# FAA.net
KiCad netlist of a schematic drawn in Altium Designer
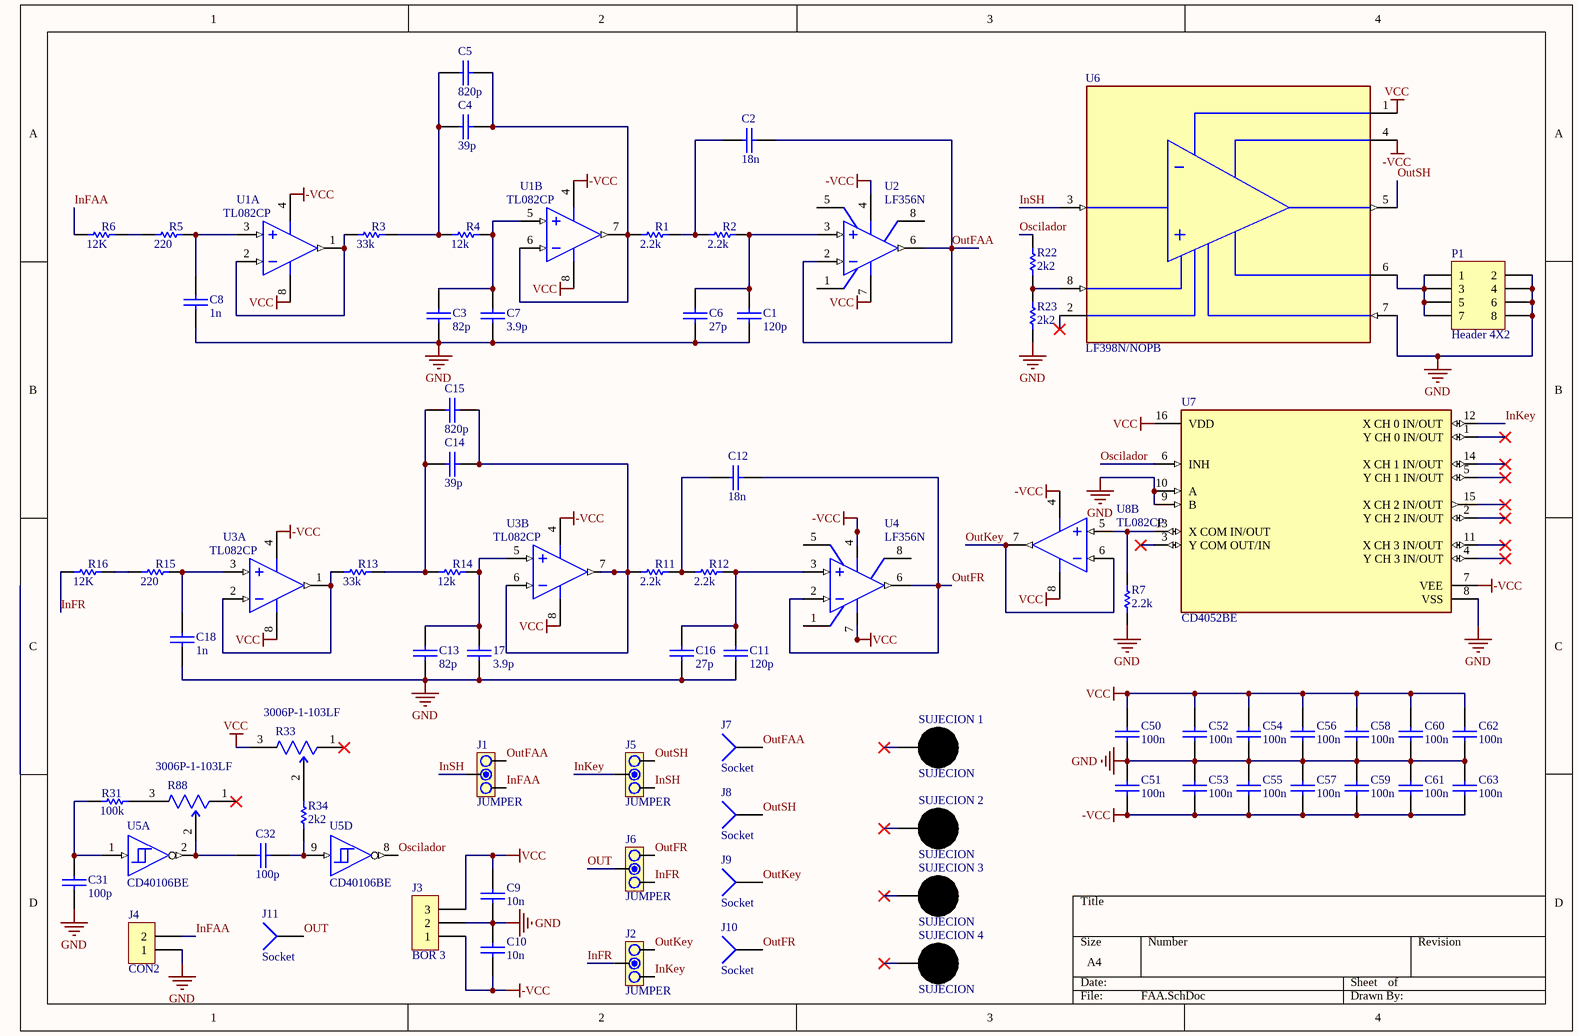
[diagram p0: FAA.SchDoc]

(export (version "E")
  (design (tool "Eeschema 10.0.6"))
  (components
    (comp (ref "17") (value "3.9p") (footprint "CAP200") (libsource (lib "LIB PIO IX") (part "CAP")))
    (comp (ref "C1") (value "120p") (footprint "CAP200") (libsource (lib "LIB PIO IX") (part "CAP")))
    (comp (ref "C2") (value "18n") (footprint "CAP200") (libsource (lib "LIB PIO IX") (part "CAP")))
    (comp (ref "C3") (value "82p") (footprint "CAP200") (libsource (lib "LIB PIO IX") (part "CAP")))
    (comp (ref "C4") (value "39p") (footprint "CAP200") (libsource (lib "LIB PIO IX") (part "CAP")))
    (comp (ref "C5") (value "820p") (footprint "CAP200") (libsource (lib "LIB PIO IX") (part "CAP")))
    (comp (ref "C6") (value "27p") (footprint "CAP200") (libsource (lib "LIB PIO IX") (part "CAP")))
    (comp (ref "C7") (value "3.9p") (footprint "CAP200") (libsource (lib "LIB PIO IX") (part "CAP")))
    (comp (ref "C8") (value "1n") (footprint "CAP200") (libsource (lib "LIB PIO IX") (part "CAP")))
    (comp (ref "C9") (value "10n") (footprint "CAP100") (libsource (lib "LIB PIO IX") (part "CAP")))
    (comp (ref "C10") (value "10n") (footprint "CAP100") (libsource (lib "LIB PIO IX") (part "CAP")))
    (comp (ref "C11") (value "120p") (footprint "CAP200") (libsource (lib "LIB PIO IX") (part "CAP")))
    (comp (ref "C12") (value "18n") (footprint "CAP200") (libsource (lib "LIB PIO IX") (part "CAP")))
    (comp (ref "C13") (value "82p") (footprint "CAP200") (libsource (lib "LIB PIO IX") (part "CAP")))
    (comp (ref "C14") (value "39p") (footprint "CAP200") (libsource (lib "LIB PIO IX") (part "CAP")))
    (comp (ref "C15") (value "820p") (footprint "CAP200") (libsource (lib "LIB PIO IX") (part "CAP")))
    (comp (ref "C16") (value "27p") (footprint "CAP200") (libsource (lib "LIB PIO IX") (part "CAP")))
    (comp (ref "C18") (value "1n") (footprint "CAP200") (libsource (lib "LIB PIO IX") (part "CAP")))
    (comp (ref "C31") (value "100p") (footprint "CAP200") (libsource (lib "LIB PIO IX") (part "CAP")))
    (comp (ref "C32") (value "100p") (footprint "CAP200") (libsource (lib "LIB PIO IX") (part "CAP")))
    (comp (ref "C50") (value "100n") (footprint "CAP100") (libsource (lib "LIB PIO IX") (part "CAP")))
    (comp (ref "C51") (value "100n") (footprint "CAP100") (libsource (lib "LIB PIO IX") (part "CAP")))
    (comp (ref "C52") (value "100n") (footprint "CAP100") (libsource (lib "LIB PIO IX") (part "CAP")))
    (comp (ref "C53") (value "100n") (footprint "CAP100") (libsource (lib "LIB PIO IX") (part "CAP")))
    (comp (ref "C54") (value "100n") (footprint "CAP100") (libsource (lib "LIB PIO IX") (part "CAP")))
    (comp (ref "C55") (value "100n") (footprint "CAP100") (libsource (lib "LIB PIO IX") (part "CAP")))
    (comp (ref "C56") (value "100n") (footprint "CAP100") (libsource (lib "LIB PIO IX") (part "CAP")))
    (comp (ref "C57") (value "100n") (footprint "CAP100") (libsource (lib "LIB PIO IX") (part "CAP")))
    (comp (ref "C58") (value "100n") (footprint "CAP100") (libsource (lib "LIB PIO IX") (part "CAP")))
    (comp (ref "C59") (value "100n") (footprint "CAP100") (libsource (lib "LIB PIO IX") (part "CAP")))
    (comp (ref "C60") (value "100n") (footprint "CAP100") (libsource (lib "LIB PIO IX") (part "CAP")))
    (comp (ref "C61") (value "100n") (footprint "CAP100") (libsource (lib "LIB PIO IX") (part "CAP")))
    (comp (ref "C62") (value "100n") (footprint "CAP100") (libsource (lib "LIB PIO IX") (part "CAP")))
    (comp (ref "C63") (value "100n") (footprint "CAP100") (libsource (lib "LIB PIO IX") (part "CAP")))
    (comp (ref "J1") (value "JUMPER") (footprint "JUMPER3") (libsource (lib "LIB PIO IX") (part "JUMPER3")))
    (comp (ref "J2") (value "JUMPER") (footprint "JUMPER3") (libsource (lib "LIB PIO IX") (part "JUMPER3")))
    (comp (ref "J3") (value "BOR 3") (footprint "BORNERA3") (libsource (lib "LIB PIO IX") (part "BORNERA 3")))
    (comp (ref "J4") (value "CON2") (footprint "SIP2") (libsource (lib "LIB PIO IX") (part "CON2")))
    (comp (ref "J5") (value "JUMPER") (footprint "JUMPER3") (libsource (lib "LIB PIO IX") (part "JUMPER3")))
    (comp (ref "J6") (value "JUMPER") (footprint "JUMPER3") (libsource (lib "LIB PIO IX") (part "JUMPER3")))
    (comp (ref "J7")
      (value "Socket")
      (footprint "PIN1")
      (fields (field (name "PUBLISHER") "Altium Limited"))
      (libsource (lib "Miscellaneous Connectors") (part "Socket"))
    )
    (comp (ref "J8")
      (value "Socket")
      (footprint "PIN1")
      (fields (field (name "PUBLISHER") "Altium Limited"))
      (libsource (lib "Miscellaneous Connectors") (part "Socket"))
    )
    (comp (ref "J9")
      (value "Socket")
      (footprint "PIN1")
      (fields (field (name "PUBLISHER") "Altium Limited"))
      (libsource (lib "Miscellaneous Connectors") (part "Socket"))
    )
    (comp (ref "J10")
      (value "Socket")
      (footprint "PIN1")
      (fields (field (name "PUBLISHER") "Altium Limited"))
      (libsource (lib "Miscellaneous Connectors") (part "Socket"))
    )
    (comp (ref "J11")
      (value "Socket")
      (footprint "PIN1")
      (fields (field (name "PUBLISHER") "Altium Limited"))
      (libsource (lib "Miscellaneous Connectors") (part "Socket"))
    )
    (comp (ref "P1")
      (value "Header 4X2")
      (footprint "HDR2X4")
      (description "Header, 4-Pin, Dual row")
      (fields (field (name "PUBLISHER") "Altium Limited"))
      (libsource (lib "Miscellaneous Connectors") (part "Header 4X2"))
    )
    (comp (ref "R1") (value "2.2k") (footprint "RES400") (libsource (lib "LIB PIO IX") (part "RES")))
    (comp (ref "R2") (value "2.2k") (footprint "RES400") (libsource (lib "LIB PIO IX") (part "RES")))
    (comp (ref "R3") (value "33k") (footprint "RES400") (libsource (lib "LIB PIO IX") (part "RES")))
    (comp (ref "R4") (value "12k") (footprint "RES400") (libsource (lib "LIB PIO IX") (part "RES")))
    (comp (ref "R5") (value "220") (footprint "RES400") (libsource (lib "LIB PIO IX") (part "RES")))
    (comp (ref "R6") (value "12K") (footprint "RES400") (libsource (lib "LIB PIO IX") (part "RES")))
    (comp (ref "R7") (value "2.2k") (footprint "RES400") (libsource (lib "LIB PIO IX") (part "RES")))
    (comp (ref "R11") (value "2.2k") (footprint "RES400") (libsource (lib "LIB PIO IX") (part "RES")))
    (comp (ref "R12") (value "2.2k") (footprint "RES400") (libsource (lib "LIB PIO IX") (part "RES")))
    (comp (ref "R13") (value "33k") (footprint "RES400") (libsource (lib "LIB PIO IX") (part "RES")))
    (comp (ref "R14") (value "12k") (footprint "RES400") (libsource (lib "LIB PIO IX") (part "RES")))
    (comp (ref "R15") (value "220") (footprint "RES400") (libsource (lib "LIB PIO IX") (part "RES")))
    (comp (ref "R16") (value "12K") (footprint "RES400") (libsource (lib "LIB PIO IX") (part "RES")))
    (comp (ref "R22") (value "2k2") (footprint "RES400") (libsource (lib "LIB PIO IX") (part "RES")))
    (comp (ref "R23") (value "2k2") (footprint "RES400") (libsource (lib "LIB PIO IX") (part "RES")))
    (comp (ref "R31") (value "100k") (footprint "RES400") (libsource (lib "LIB PIO IX") (part "RES")))
    (comp (ref "R33")
      (value "3006P-1-103LF")
      (footprint "FP-3006P-MFG")
      (description "TRIMMER 10KOHM 0.75W PC PIN SIDE")
      (fields (field (name "TOLERANCE") "10%"))
      (libsource (lib "Altium Content Vault") (part "ad0de4570dda44d2fdef8f57041519a"))
    )
    (comp (ref "R34") (value "2k2") (footprint "RES400") (libsource (lib "LIB PIO IX") (part "RES")))
    (comp (ref "R88")
      (value "3006P-1-103LF")
      (footprint "FP-3006P-MFG")
      (description "TRIMMER 10KOHM 0.75W PC PIN SIDE")
      (fields (field (name "TOLERANCE") "10%"))
      (libsource (lib "Altium Content Vault") (part "ad0de4570dda44d2fdef8f57041519a"))
    )
    (comp (ref "SUJECION 1")
      (value "SUJECION")
      (footprint "SUJECION (5.00MM - 3.50MM)")
      (libsource (lib "LIB2013") (part "SUJECION"))
    )
    (comp (ref "SUJECION 2")
      (value "SUJECION")
      (footprint "SUJECION (5.00MM - 3.50MM)")
      (libsource (lib "LIB2013") (part "SUJECION"))
    )
    (comp (ref "SUJECION 3")
      (value "SUJECION")
      (footprint "SUJECION (5.00MM - 3.50MM)")
      (libsource (lib "LIB2013") (part "SUJECION"))
    )
    (comp (ref "SUJECION 4")
      (value "SUJECION")
      (footprint "SUJECION (5.00MM - 3.50MM)")
      (libsource (lib "LIB2013") (part "SUJECION"))
    )
    (comp (ref "U1")
      (value "TL082CP")
      (footprint "P0008A")
      (description "JFET-Input Operational Amplifier, 7 to 36 V, 0 to 70 degC, 8-pin DIP (P8), Pb-Free (RoHS)")
      (fields (field (name "MANUFACTURER") "Texas Instruments"))
      (libsource (lib "Altium Content Vault") (part "TI-AMP-D6-2-8_D"))
    )
    (comp (ref "U2")
      (value "LF356N")
      (footprint "P0008A")
      (description "JFET Input Operational Amplifier, 8-pin MDIP")
      (fields (field (name "MANUFACTURER") "Texas Instruments"))
      (libsource (lib "Altium Content Vault") (part "AMP-OPA-LF156-8"))
    )
    (comp (ref "U3")
      (value "TL082CP")
      (footprint "P0008A")
      (description "JFET-Input Operational Amplifier, 7 to 36 V, 0 to 70 degC, 8-pin DIP (P8), Pb-Free (RoHS)")
      (fields (field (name "MANUFACTURER") "Texas Instruments"))
      (libsource (lib "Altium Content Vault") (part "TI-AMP-D6-2-8_D"))
    )
    (comp (ref "U4")
      (value "LF356N")
      (footprint "P0008A")
      (description "JFET Input Operational Amplifier, 8-pin MDIP")
      (fields (field (name "MANUFACTURER") "Texas Instruments"))
      (libsource (lib "Altium Content Vault") (part "AMP-OPA-LF156-8"))
    )
    (comp (ref "U5")
      (value "CD40106BE")
      (footprint "N0014A")
      (description "CMOS Hex Schmitt Triggers, N0014A, TUBE")
      (fields
        (field (name "MANUFACTURER") "Texas Instruments")
        (field (name "GENERIC PART NUMBER") "CD40106B")
      )
      (libsource (lib "Altium Content Vault") (part "TI-CD40XXXB-14-SCHMITT"))
    )
    (comp (ref "U6")
      (value "LF398N/NOPB")
      (footprint "FP-P0008A-MFG")
      (description "IC OPAMP SAMPL/HOLD 1 CIRC 8DIP")
      (libsource (lib "Altium Content Vault") (part "663395f396e52967eeae42d09f15be4"))
    )
    (comp (ref "U7")
      (value "CD4052BE")
      (footprint "FP-N0016A-MFG")
      (description "IC MUX/DEMUX DUAL 4X1 16DIP")
      (libsource (lib "Altium Content Vault") (part "f592c568caf548e7f28197573c85c05"))
    )
    (comp (ref "U8")
      (value "TL082CP")
      (footprint "P0008A")
      (description "JFET-Input Operational Amplifier, 7 to 36 V, 0 to 70 degC, 8-pin DIP (P8), Pb-Free (RoHS)")
      (fields (field (name "MANUFACTURER") "Texas Instruments"))
      (libsource (lib "Altium Content Vault") (part "TI-AMP-D6-2-8_D"))
    )
  )
  (nets
    (net (code "1") (name "-VCC") (class "Default")
      (node (ref "C10") (pin "2") (pinfunction "2_2") (pintype "passive"))
      (node (ref "C51") (pin "2") (pinfunction "2_2") (pintype "passive"))
      (node (ref "C53") (pin "2") (pinfunction "2_2") (pintype "passive"))
      (node (ref "C55") (pin "2") (pinfunction "2_2") (pintype "passive"))
      (node (ref "C57") (pin "2") (pinfunction "2_2") (pintype "passive"))
      (node (ref "C59") (pin "2") (pinfunction "2_2") (pintype "passive"))
      (node (ref "C61") (pin "2") (pinfunction "2_2") (pintype "passive"))
      (node (ref "C63") (pin "2") (pinfunction "2_2") (pintype "passive"))
      (node (ref "J3") (pin "1") (pinfunction "1_1") (pintype "passive"))
      (node (ref "U1") (pin "4") (pinfunction "VCC-_4") (pintype "power_in"))
      (node (ref "U2") (pin "4") (pinfunction "V-_4") (pintype "power_in"))
      (node (ref "U3") (pin "4") (pinfunction "VCC-_4") (pintype "power_in"))
      (node (ref "U4") (pin "4") (pinfunction "V-_4") (pintype "power_in"))
      (node (ref "U6") (pin "4") (pinfunction "V-_4") (pintype "power_in"))
      (node (ref "U7") (pin "7") (pinfunction "VEE_7") (pintype "power_in"))
      (node (ref "U8") (pin "4") (pinfunction "VCC-_4") (pintype "power_in"))
    )
    (net (code "2") (name "/InFAA") (class "Default")
      (node (ref "J1") (pin "3") (pinfunction "3_3") (pintype "passive"))
      (node (ref "J4") (pin "2") (pinfunction "2_2") (pintype "passive"))
      (node (ref "R6") (pin "1") (pinfunction "1_1") (pintype "passive"))
    )
    (net (code "3") (name "/InFR") (class "Default")
      (node (ref "J2") (pin "2") (pinfunction "2_2") (pintype "passive"))
      (node (ref "J6") (pin "3") (pinfunction "3_3") (pintype "passive"))
      (node (ref "R16") (pin "1") (pinfunction "1_1") (pintype "passive"))
    )
    (net (code "4") (name "/InKey") (class "Default")
      (node (ref "J2") (pin "3") (pinfunction "3_3") (pintype "passive"))
      (node (ref "J5") (pin "2") (pinfunction "2_2") (pintype "passive"))
      (node (ref "U7") (pin "12") (pinfunction "X_CH_0_IN/OUT_12") (pintype "bidirectional"))
    )
    (net (code "5") (name "/InSH") (class "Default")
      (node (ref "J1") (pin "2") (pinfunction "2_2") (pintype "passive"))
      (node (ref "J5") (pin "3") (pinfunction "3_3") (pintype "passive"))
      (node (ref "U6") (pin "3") (pinfunction "INPUT_3") (pintype "input"))
    )
    (net (code "6") (name "/OUT") (class "Default")
      (node (ref "J11") (pin "1") (pinfunction "1_1") (pintype "passive"))
      (node (ref "J6") (pin "2") (pinfunction "2_2") (pintype "passive"))
    )
    (net (code "7") (name "/Oscilador") (class "Default")
      (node (ref "R22") (pin "1") (pinfunction "1_1") (pintype "passive"))
      (node (ref "U5") (pin "8") (pinfunction "J=~{D}_8") (pintype "output"))
      (node (ref "U7") (pin "6") (pinfunction "INH_6") (pintype "input"))
    )
    (net (code "8") (name "/OutFAA") (class "Default")
      (node (ref "C2") (pin "2") (pinfunction "2_2") (pintype "passive"))
      (node (ref "J1") (pin "1") (pinfunction "1_1") (pintype "passive"))
      (node (ref "J7") (pin "1") (pinfunction "1_1") (pintype "passive"))
      (node (ref "U2") (pin "2") (pinfunction "IN-_2") (pintype "input"))
      (node (ref "U2") (pin "6") (pinfunction "OUT_6") (pintype "output"))
    )
    (net (code "9") (name "/OutFR") (class "Default")
      (node (ref "C12") (pin "2") (pinfunction "2_2") (pintype "passive"))
      (node (ref "J10") (pin "1") (pinfunction "1_1") (pintype "passive"))
      (node (ref "J6") (pin "1") (pinfunction "1_1") (pintype "passive"))
      (node (ref "U4") (pin "2") (pinfunction "IN-_2") (pintype "input"))
      (node (ref "U4") (pin "6") (pinfunction "OUT_6") (pintype "output"))
    )
    (net (code "10") (name "/OutKey") (class "Default")
      (node (ref "J2") (pin "1") (pinfunction "1_1") (pintype "passive"))
      (node (ref "J9") (pin "1") (pinfunction "1_1") (pintype "passive"))
      (node (ref "U8") (pin "6") (pinfunction "IN2-_6") (pintype "input"))
      (node (ref "U8") (pin "7") (pinfunction "OUT2_7") (pintype "output"))
    )
    (net (code "11") (name "/OutSH") (class "Default")
      (node (ref "J5") (pin "1") (pinfunction "1_1") (pintype "passive"))
      (node (ref "J8") (pin "1") (pinfunction "1_1") (pintype "passive"))
      (node (ref "U6") (pin "5") (pinfunction "OUTPUT_5") (pintype "output"))
    )
    (net (code "12") (name "GND") (class "Default")
      (node (ref "17") (pin "2") (pinfunction "2_2") (pintype "passive"))
      (node (ref "C1") (pin "2") (pinfunction "2_2") (pintype "passive"))
      (node (ref "C10") (pin "1") (pinfunction "1_1") (pintype "passive"))
      (node (ref "C11") (pin "2") (pinfunction "2_2") (pintype "passive"))
      (node (ref "C13") (pin "2") (pinfunction "2_2") (pintype "passive"))
      (node (ref "C16") (pin "2") (pinfunction "2_2") (pintype "passive"))
      (node (ref "C18") (pin "2") (pinfunction "2_2") (pintype "passive"))
      (node (ref "C3") (pin "2") (pinfunction "2_2") (pintype "passive"))
      (node (ref "C31") (pin "2") (pinfunction "2_2") (pintype "passive"))
      (node (ref "C50") (pin "2") (pinfunction "2_2") (pintype "passive"))
      (node (ref "C51") (pin "1") (pinfunction "1_1") (pintype "passive"))
      (node (ref "C52") (pin "2") (pinfunction "2_2") (pintype "passive"))
      (node (ref "C53") (pin "1") (pinfunction "1_1") (pintype "passive"))
      (node (ref "C54") (pin "2") (pinfunction "2_2") (pintype "passive"))
      (node (ref "C55") (pin "1") (pinfunction "1_1") (pintype "passive"))
      (node (ref "C56") (pin "2") (pinfunction "2_2") (pintype "passive"))
      (node (ref "C57") (pin "1") (pinfunction "1_1") (pintype "passive"))
      (node (ref "C58") (pin "2") (pinfunction "2_2") (pintype "passive"))
      (node (ref "C59") (pin "1") (pinfunction "1_1") (pintype "passive"))
      (node (ref "C6") (pin "2") (pinfunction "2_2") (pintype "passive"))
      (node (ref "C60") (pin "2") (pinfunction "2_2") (pintype "passive"))
      (node (ref "C61") (pin "1") (pinfunction "1_1") (pintype "passive"))
      (node (ref "C62") (pin "2") (pinfunction "2_2") (pintype "passive"))
      (node (ref "C63") (pin "1") (pinfunction "1_1") (pintype "passive"))
      (node (ref "C7") (pin "2") (pinfunction "2_2") (pintype "passive"))
      (node (ref "C8") (pin "2") (pinfunction "2_2") (pintype "passive"))
      (node (ref "C9") (pin "2") (pinfunction "2_2") (pintype "passive"))
      (node (ref "J3") (pin "2") (pinfunction "2_2") (pintype "passive"))
      (node (ref "J4") (pin "1") (pinfunction "1_1") (pintype "passive"))
      (node (ref "P1") (pin "2") (pinfunction "2_2") (pintype "passive"))
      (node (ref "P1") (pin "4") (pinfunction "4_4") (pintype "passive"))
      (node (ref "P1") (pin "6") (pinfunction "6_6") (pintype "passive"))
      (node (ref "P1") (pin "8") (pinfunction "8_8") (pintype "passive"))
      (node (ref "R23") (pin "2") (pinfunction "2_2") (pintype "passive"))
      (node (ref "R7") (pin "1") (pinfunction "1_1") (pintype "passive"))
      (node (ref "U6") (pin "7") (pinfunction "LOGIC_REFERENCE_7") (pintype "input"))
      (node (ref "U7") (pin "10") (pinfunction "A_10") (pintype "input"))
      (node (ref "U7") (pin "8") (pinfunction "VSS_8") (pintype "power_in"))
      (node (ref "U7") (pin "9") (pinfunction "B_9") (pintype "input"))
    )
    (net (code "13") (name "Net-(C2-Pad1)") (class "Default")
      (node (ref "C2") (pin "1") (pinfunction "1_1") (pintype "passive"))
      (node (ref "R1") (pin "2") (pinfunction "2_2") (pintype "passive"))
      (node (ref "R2") (pin "1") (pinfunction "1_1") (pintype "passive"))
    )
    (net (code "14") (name "Net-(C4-Pad1)") (class "Default")
      (node (ref "C4") (pin "1") (pinfunction "1_1") (pintype "passive"))
      (node (ref "C5") (pin "1") (pinfunction "1_1") (pintype "passive"))
      (node (ref "R3") (pin "2") (pinfunction "2_2") (pintype "passive"))
      (node (ref "R4") (pin "1") (pinfunction "1_1") (pintype "passive"))
    )
    (net (code "15") (name "Net-(C12-Pad1)") (class "Default")
      (node (ref "C12") (pin "1") (pinfunction "1_1") (pintype "passive"))
      (node (ref "R11") (pin "2") (pinfunction "2_2") (pintype "passive"))
      (node (ref "R12") (pin "1") (pinfunction "1_1") (pintype "passive"))
    )
    (net (code "16") (name "Net-(C14-Pad1)") (class "Default")
      (node (ref "C14") (pin "1") (pinfunction "1_1") (pintype "passive"))
      (node (ref "C15") (pin "1") (pinfunction "1_1") (pintype "passive"))
      (node (ref "R13") (pin "2") (pinfunction "2_2") (pintype "passive"))
      (node (ref "R14") (pin "1") (pinfunction "1_1") (pintype "passive"))
    )
    (net (code "17") (name "Net-(R5-Pad1)") (class "Default")
      (node (ref "R5") (pin "1") (pinfunction "1_1") (pintype "passive"))
      (node (ref "R6") (pin "2") (pinfunction "2_2") (pintype "passive"))
    )
    (net (code "18") (name "Net-(R15-Pad1)") (class "Default")
      (node (ref "R15") (pin "1") (pinfunction "1_1") (pintype "passive"))
      (node (ref "R16") (pin "2") (pinfunction "2_2") (pintype "passive"))
    )
    (net (code "19") (name "Net-(R33-WIPER)") (class "Default")
      (node (ref "R33") (pin "2") (pinfunction "WIPER_2") (pintype "passive"))
      (node (ref "R34") (pin "2") (pinfunction "2_2") (pintype "passive"))
    )
    (net (code "20") (name "Net-(R88-CW)") (class "Default")
      (node (ref "R31") (pin "2") (pinfunction "2_2") (pintype "passive"))
      (node (ref "R88") (pin "3") (pinfunction "CW_3") (pintype "passive"))
    )
    (net (code "21") (name "Net-(R88-WIPER)") (class "Default")
      (node (ref "C32") (pin "1") (pinfunction "1_1") (pintype "passive"))
      (node (ref "R88") (pin "2") (pinfunction "WIPER_2") (pintype "passive"))
      (node (ref "U5") (pin "2") (pinfunction "G=~{A}_2") (pintype "output"))
    )
    (net (code "22") (name "Net-(U1A-IN1+)") (class "Default")
      (node (ref "C8") (pin "1") (pinfunction "1_1") (pintype "passive"))
      (node (ref "R5") (pin "2") (pinfunction "2_2") (pintype "passive"))
      (node (ref "U1") (pin "3") (pinfunction "IN1+_3") (pintype "input"))
    )
    (net (code "23") (name "Net-(U1A-IN1-)") (class "Default")
      (node (ref "R3") (pin "1") (pinfunction "1_1") (pintype "passive"))
      (node (ref "U1") (pin "1") (pinfunction "OUT1_1") (pintype "output"))
      (node (ref "U1") (pin "2") (pinfunction "IN1-_2") (pintype "input"))
    )
    (net (code "24") (name "Net-(U1B-IN2+)") (class "Default")
      (node (ref "C3") (pin "1") (pinfunction "1_1") (pintype "passive"))
      (node (ref "C7") (pin "1") (pinfunction "1_1") (pintype "passive"))
      (node (ref "R4") (pin "2") (pinfunction "2_2") (pintype "passive"))
      (node (ref "U1") (pin "5") (pinfunction "IN2+_5") (pintype "input"))
    )
    (net (code "25") (name "Net-(U1B-IN2-)") (class "Default")
      (node (ref "C4") (pin "2") (pinfunction "2_2") (pintype "passive"))
      (node (ref "C5") (pin "2") (pinfunction "2_2") (pintype "passive"))
      (node (ref "R1") (pin "1") (pinfunction "1_1") (pintype "passive"))
      (node (ref "U1") (pin "6") (pinfunction "IN2-_6") (pintype "input"))
      (node (ref "U1") (pin "7") (pinfunction "OUT2_7") (pintype "output"))
    )
    (net (code "26") (name "Net-(U2-IN+)") (class "Default")
      (node (ref "C1") (pin "1") (pinfunction "1_1") (pintype "passive"))
      (node (ref "C6") (pin "1") (pinfunction "1_1") (pintype "passive"))
      (node (ref "R2") (pin "2") (pinfunction "2_2") (pintype "passive"))
      (node (ref "U2") (pin "3") (pinfunction "IN+_3") (pintype "input"))
    )
    (net (code "27") (name "Net-(U3A-IN1+)") (class "Default")
      (node (ref "C18") (pin "1") (pinfunction "1_1") (pintype "passive"))
      (node (ref "R15") (pin "2") (pinfunction "2_2") (pintype "passive"))
      (node (ref "U3") (pin "3") (pinfunction "IN1+_3") (pintype "input"))
    )
    (net (code "28") (name "Net-(U3A-IN1-)") (class "Default")
      (node (ref "R13") (pin "1") (pinfunction "1_1") (pintype "passive"))
      (node (ref "U3") (pin "1") (pinfunction "OUT1_1") (pintype "output"))
      (node (ref "U3") (pin "2") (pinfunction "IN1-_2") (pintype "input"))
    )
    (net (code "29") (name "Net-(U3B-IN2+)") (class "Default")
      (node (ref "17") (pin "1") (pinfunction "1_1") (pintype "passive"))
      (node (ref "C13") (pin "1") (pinfunction "1_1") (pintype "passive"))
      (node (ref "R14") (pin "2") (pinfunction "2_2") (pintype "passive"))
      (node (ref "U3") (pin "5") (pinfunction "IN2+_5") (pintype "input"))
    )
    (net (code "30") (name "Net-(U3B-IN2-)") (class "Default")
      (node (ref "C14") (pin "2") (pinfunction "2_2") (pintype "passive"))
      (node (ref "C15") (pin "2") (pinfunction "2_2") (pintype "passive"))
      (node (ref "R11") (pin "1") (pinfunction "1_1") (pintype "passive"))
      (node (ref "U3") (pin "6") (pinfunction "IN2-_6") (pintype "input"))
      (node (ref "U3") (pin "7") (pinfunction "OUT2_7") (pintype "output"))
    )
    (net (code "31") (name "Net-(U4-IN+)") (class "Default")
      (node (ref "C11") (pin "1") (pinfunction "1_1") (pintype "passive"))
      (node (ref "C16") (pin "1") (pinfunction "1_1") (pintype "passive"))
      (node (ref "R12") (pin "2") (pinfunction "2_2") (pintype "passive"))
      (node (ref "U4") (pin "3") (pinfunction "IN+_3") (pintype "input"))
    )
    (net (code "32") (name "Net-(U5A-A)") (class "Default")
      (node (ref "C31") (pin "1") (pinfunction "1_1") (pintype "passive"))
      (node (ref "R31") (pin "1") (pinfunction "1_1") (pintype "passive"))
      (node (ref "U5") (pin "1") (pinfunction "A_1") (pintype "input"))
    )
    (net (code "33") (name "Net-(U5D-D)") (class "Default")
      (node (ref "C32") (pin "2") (pinfunction "2_2") (pintype "passive"))
      (node (ref "R34") (pin "1") (pinfunction "1_1") (pintype "passive"))
      (node (ref "U5") (pin "9") (pinfunction "D_9") (pintype "input"))
    )
    (net (code "34") (name "Net-(U6-Ch)") (class "Default")
      (node (ref "P1") (pin "1") (pinfunction "1_1") (pintype "passive"))
      (node (ref "P1") (pin "3") (pinfunction "3_3") (pintype "passive"))
      (node (ref "P1") (pin "5") (pinfunction "5_5") (pintype "passive"))
      (node (ref "P1") (pin "7") (pinfunction "7_7") (pintype "passive"))
      (node (ref "U6") (pin "6") (pinfunction "Ch_6") (pintype "passive"))
    )
    (net (code "35") (name "Net-(U6-LOGIC)") (class "Default")
      (node (ref "R22") (pin "2") (pinfunction "2_2") (pintype "passive"))
      (node (ref "R23") (pin "1") (pinfunction "1_1") (pintype "passive"))
      (node (ref "U6") (pin "8") (pinfunction "LOGIC_8") (pintype "input"))
    )
    (net (code "36") (name "Net-(U7-X_COM_IN{slash}OUT)") (class "Default")
      (node (ref "R7") (pin "2") (pinfunction "2_2") (pintype "passive"))
      (node (ref "U7") (pin "13") (pinfunction "X_COM_IN/OUT_13") (pintype "bidirectional"))
      (node (ref "U8") (pin "5") (pinfunction "IN2+_5") (pintype "input"))
    )
    (net (code "37") (name "VCC") (class "Default")
      (node (ref "C50") (pin "1") (pinfunction "1_1") (pintype "passive"))
      (node (ref "C52") (pin "1") (pinfunction "1_1") (pintype "passive"))
      (node (ref "C54") (pin "1") (pinfunction "1_1") (pintype "passive"))
      (node (ref "C56") (pin "1") (pinfunction "1_1") (pintype "passive"))
      (node (ref "C58") (pin "1") (pinfunction "1_1") (pintype "passive"))
      (node (ref "C60") (pin "1") (pinfunction "1_1") (pintype "passive"))
      (node (ref "C62") (pin "1") (pinfunction "1_1") (pintype "passive"))
      (node (ref "C9") (pin "1") (pinfunction "1_1") (pintype "passive"))
      (node (ref "J3") (pin "3") (pinfunction "3_3") (pintype "passive"))
      (node (ref "R33") (pin "3") (pinfunction "CW_3") (pintype "passive"))
      (node (ref "U1") (pin "8") (pinfunction "VCC+_8") (pintype "power_in"))
      (node (ref "U2") (pin "7") (pinfunction "V+_7") (pintype "power_in"))
      (node (ref "U3") (pin "8") (pinfunction "VCC+_8") (pintype "power_in"))
      (node (ref "U4") (pin "7") (pinfunction "V+_7") (pintype "power_in"))
      (node (ref "U6") (pin "1") (pinfunction "V+_1") (pintype "power_in"))
      (node (ref "U7") (pin "16") (pinfunction "VDD_16") (pintype "power_in"))
      (node (ref "U8") (pin "8") (pinfunction "VCC+_8") (pintype "power_in"))
    )
    (net (code "38") (name "unconnected-(R33-CCW-Pad1)") (class "Default")
      (node (ref "R33") (pin "1") (pinfunction "CCW_1") (pintype "passive+no_connect"))
    )
    (net (code "39") (name "unconnected-(R88-CCW-Pad1)") (class "Default")
      (node (ref "R88") (pin "1") (pinfunction "CCW_1") (pintype "passive+no_connect"))
    )
    (net (code "40") (name "unconnected-(SUJECION 1-Pad1)") (class "Default")
      (node (ref "SUJECION 1") (pin "1") (pinfunction "1_1") (pintype "passive+no_connect"))
    )
    (net (code "41") (name "unconnected-(SUJECION 2-Pad1)") (class "Default")
      (node (ref "SUJECION 2") (pin "1") (pinfunction "1_1") (pintype "passive+no_connect"))
    )
    (net (code "42") (name "unconnected-(SUJECION 3-Pad1)") (class "Default")
      (node (ref "SUJECION 3") (pin "1") (pinfunction "1_1") (pintype "passive+no_connect"))
    )
    (net (code "43") (name "unconnected-(SUJECION 4-Pad1)") (class "Default")
      (node (ref "SUJECION 4") (pin "1") (pinfunction "1_1") (pintype "passive+no_connect"))
    )
    (net (code "44") (name "unconnected-(U2-BAL-Pad1)") (class "Default")
      (node (ref "U2") (pin "1") (pinfunction "BAL_1") (pintype "passive"))
    )
    (net (code "45") (name "unconnected-(U2-BAL-Pad5)") (class "Default")
      (node (ref "U2") (pin "5") (pinfunction "BAL_5") (pintype "passive"))
    )
    (net (code "46") (name "unconnected-(U2-NC-Pad8)") (class "Default")
      (node (ref "U2") (pin "8") (pinfunction "NC_8") (pintype "passive"))
    )
    (net (code "47") (name "unconnected-(U4-BAL-Pad1)") (class "Default")
      (node (ref "U4") (pin "1") (pinfunction "BAL_1") (pintype "passive"))
    )
    (net (code "48") (name "unconnected-(U4-BAL-Pad5)") (class "Default")
      (node (ref "U4") (pin "5") (pinfunction "BAL_5") (pintype "passive"))
    )
    (net (code "49") (name "unconnected-(U4-NC-Pad8)") (class "Default")
      (node (ref "U4") (pin "8") (pinfunction "NC_8") (pintype "passive"))
    )
    (net (code "50") (name "unconnected-(U6-OFFSET_ADJUST-Pad2)") (class "Default")
      (node (ref "U6") (pin "2") (pinfunction "OFFSET_ADJUST_2") (pintype "passive+no_connect"))
    )
    (net (code "51") (name "unconnected-(U7-X_CH_1_IN{slash}OUT-Pad14)") (class "Default")
      (node (ref "U7") (pin "14") (pinfunction "X_CH_1_IN/OUT_14") (pintype "bidirectional+no_connect"))
    )
    (net (code "52") (name "unconnected-(U7-X_CH_2_IN{slash}OUT-Pad15)") (class "Default")
      (node (ref "U7") (pin "15") (pinfunction "X_CH_2_IN/OUT_15") (pintype "output+no_connect"))
    )
    (net (code "53") (name "unconnected-(U7-X_CH_3_IN{slash}OUT-Pad11)") (class "Default")
      (node (ref "U7") (pin "11") (pinfunction "X_CH_3_IN/OUT_11") (pintype "bidirectional+no_connect"))
    )
    (net (code "54") (name "unconnected-(U7-Y_CH_0_IN{slash}OUT-Pad1)") (class "Default")
      (node (ref "U7") (pin "1") (pinfunction "Y_CH_0_IN/OUT_1") (pintype "bidirectional+no_connect"))
    )
    (net (code "55") (name "unconnected-(U7-Y_CH_1_IN{slash}OUT-Pad5)") (class "Default")
      (node (ref "U7") (pin "5") (pinfunction "Y_CH_1_IN/OUT_5") (pintype "bidirectional+no_connect"))
    )
    (net (code "56") (name "unconnected-(U7-Y_CH_2_IN{slash}OUT-Pad2)") (class "Default")
      (node (ref "U7") (pin "2") (pinfunction "Y_CH_2_IN/OUT_2") (pintype "bidirectional+no_connect"))
    )
    (net (code "57") (name "unconnected-(U7-Y_CH_3_IN{slash}OUT-Pad4)") (class "Default")
      (node (ref "U7") (pin "4") (pinfunction "Y_CH_3_IN/OUT_4") (pintype "bidirectional+no_connect"))
    )
    (net (code "58") (name "unconnected-(U7-Y_COM_OUT{slash}IN-Pad3)") (class "Default")
      (node (ref "U7") (pin "3") (pinfunction "Y_COM_OUT/IN_3") (pintype "bidirectional+no_connect"))
    )
  )
)
